# XICIE_AFE_SMD_revA.net
KiCad netlist of a schematic drawn in EAGLE
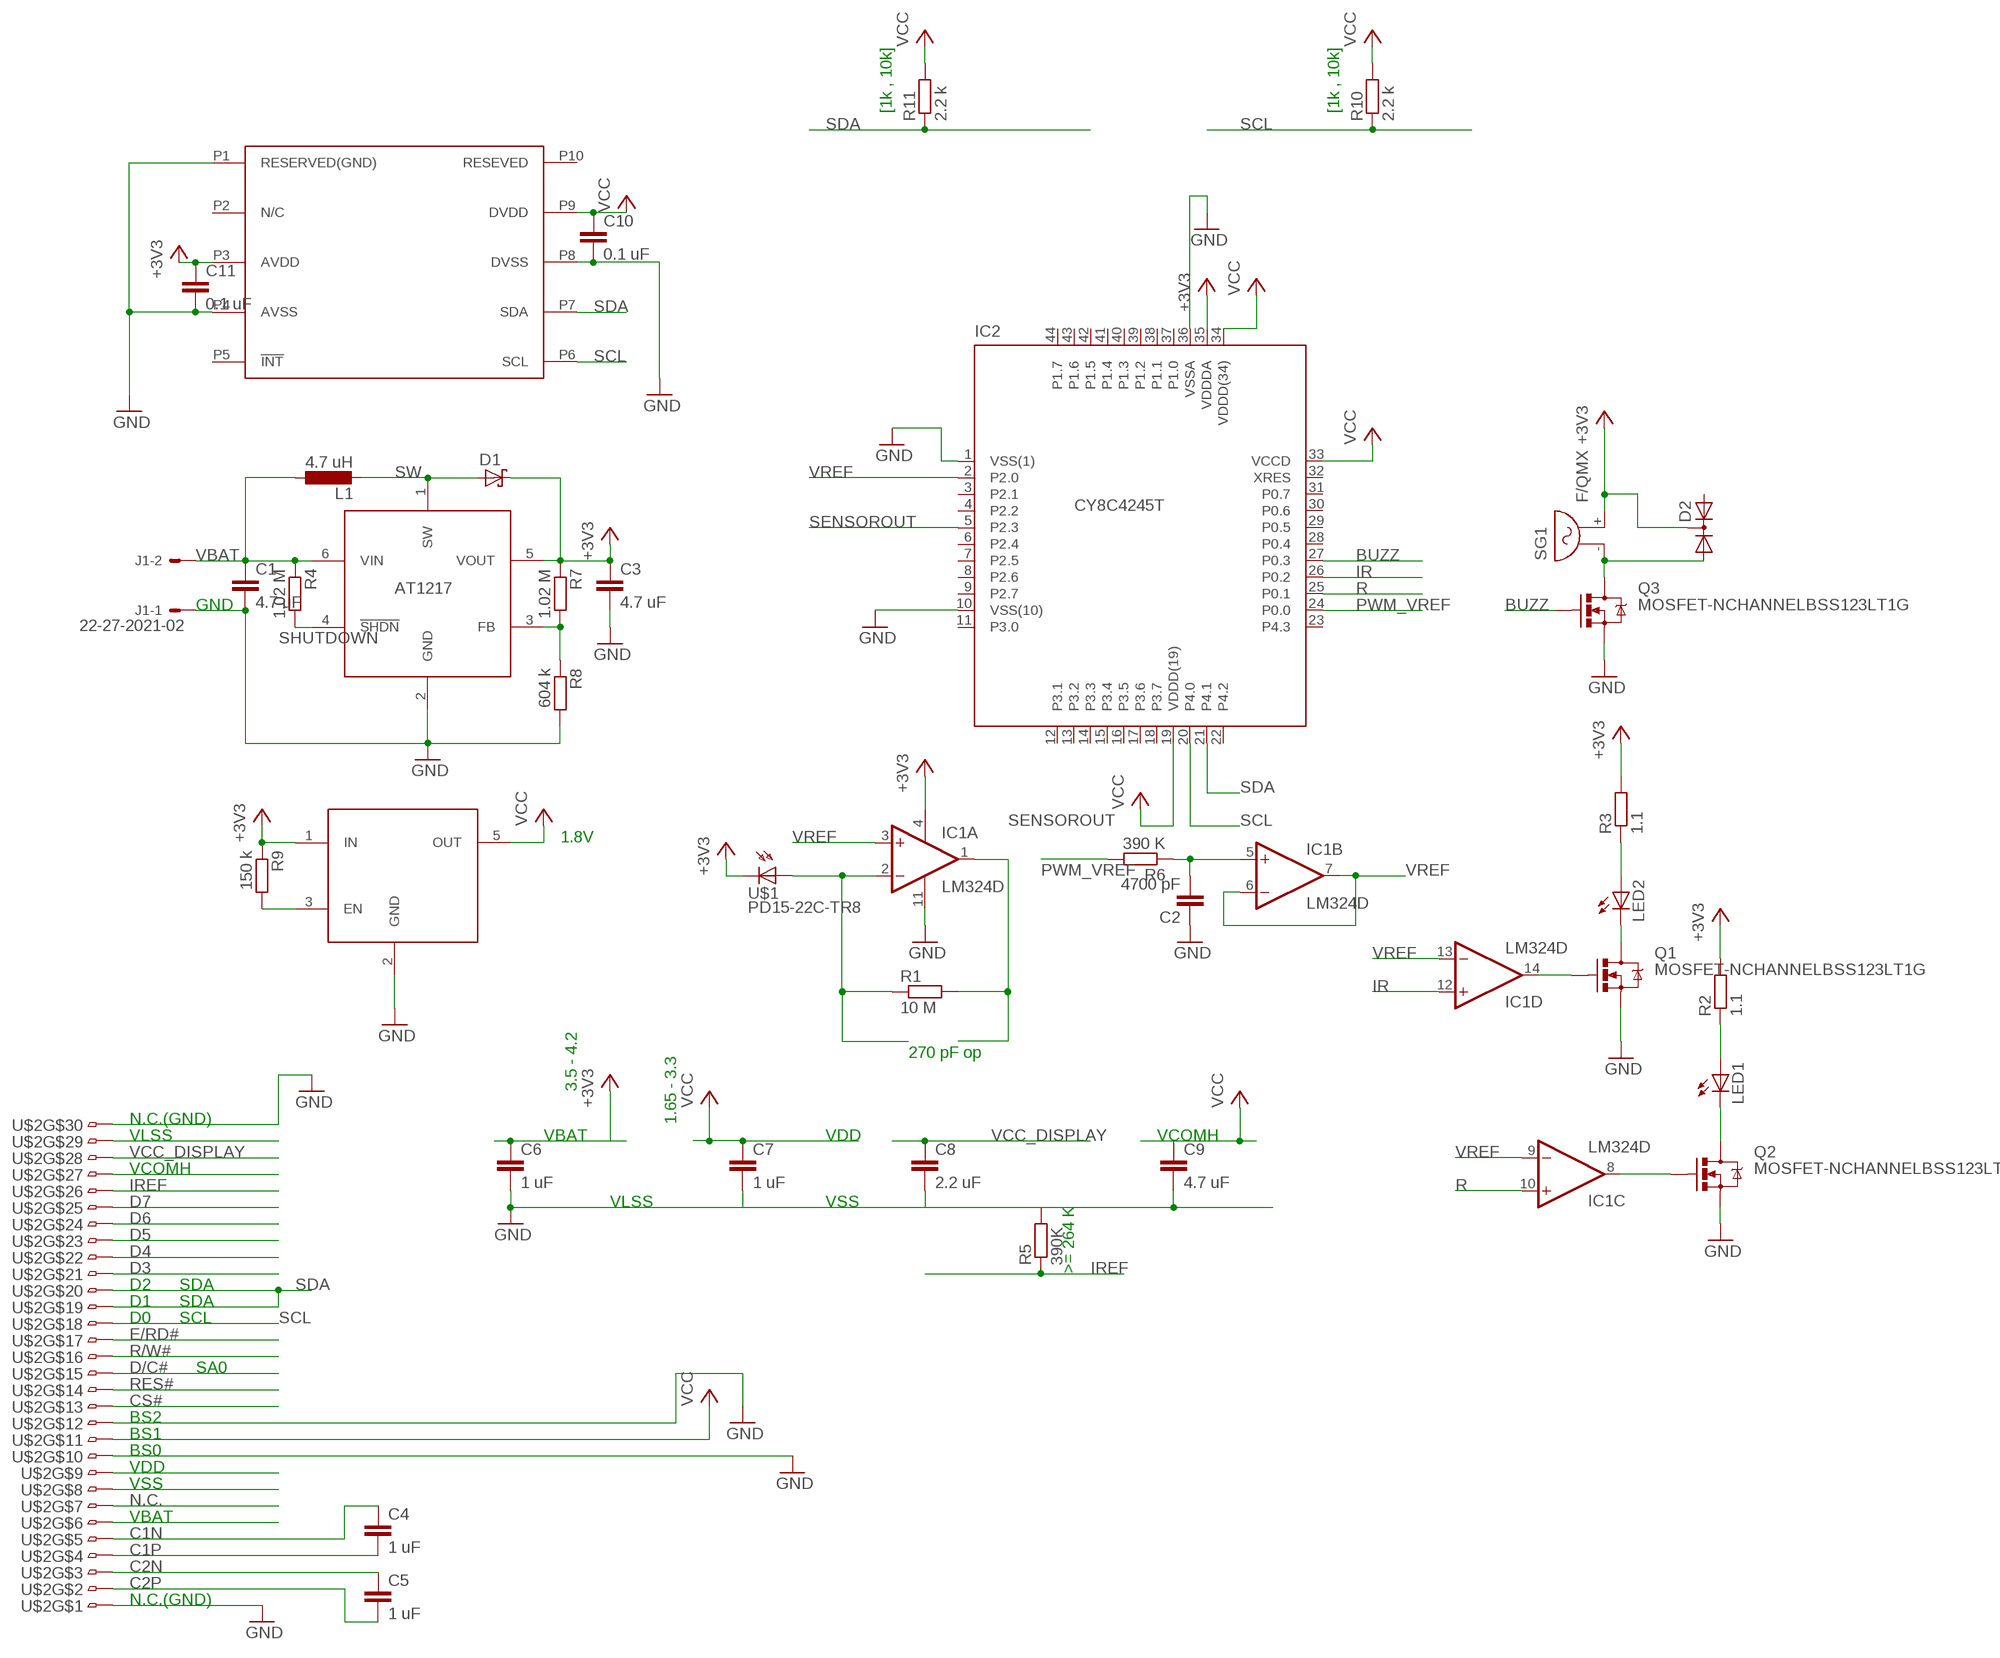
[diagram p0: schematic, sheet 1]

(export (version "E")
  (design (tool "Eeschema 10.0.6"))
  (components
    (comp (ref "C1")
      (value "4.7 uF")
      (footprint "eagle-import:C0603")
      (libsource (lib "eagle-import") (part "C-EUC0603"))
    )
    (comp (ref "C2")
      (value "4700 pF")
      (footprint "eagle-import:C0402")
      (libsource (lib "eagle-import") (part "C-EUC0402"))
    )
    (comp (ref "C3")
      (value "4.7 uF")
      (footprint "eagle-import:C0603")
      (libsource (lib "eagle-import") (part "C-EUC0603"))
    )
    (comp (ref "C4")
      (value "1 uF")
      (footprint "eagle-import:C0402")
      (libsource (lib "eagle-import") (part "C-EUC0402"))
    )
    (comp (ref "C5")
      (value "1 uF")
      (footprint "eagle-import:C0402")
      (libsource (lib "eagle-import") (part "C-EUC0402"))
    )
    (comp (ref "C6")
      (value "1 uF")
      (footprint "eagle-import:C0402")
      (libsource (lib "eagle-import") (part "C-EUC0402"))
    )
    (comp (ref "C7")
      (value "1 uF")
      (footprint "eagle-import:C0402")
      (libsource (lib "eagle-import") (part "C-EUC0402"))
    )
    (comp (ref "C8")
      (value "2.2 uF")
      (footprint "eagle-import:C0603")
      (libsource (lib "eagle-import") (part "C-EUC0603"))
    )
    (comp (ref "C9")
      (value "4.7 uF")
      (footprint "eagle-import:C0603")
      (libsource (lib "eagle-import") (part "C-EUC0603"))
    )
    (comp (ref "C10")
      (value "0.1 uF")
      (footprint "eagle-import:C0402")
      (libsource (lib "eagle-import") (part "C-EUC0402"))
    )
    (comp (ref "C11")
      (value "0.1 uF")
      (footprint "eagle-import:C0402")
      (libsource (lib "eagle-import") (part "C-EUC0402"))
    )
    (comp (ref "D1")
      (value "SCHOTTKY-DIODESMD")
      (footprint "eagle-import:SMINI2-F5-B")
      (libsource (lib "eagle-import") (part "SCHOTTKY-DIODESMD"))
    )
    (comp (ref "D2")
      (value "DIODE-2AC|CASOT23")
      (footprint "eagle-import:SOT23")
      (libsource (lib "eagle-import") (part "DIODE-2AC|CASOT23"))
    )
    (comp (ref "IC1")
      (value "LM324D")
      (footprint "eagle-import:SO14")
      (libsource (lib "eagle-import") (part "LM324D"))
    )
    (comp (ref "IC2")
      (value "CY8C4245T")
      (footprint "eagle-import:TQFP44")
      (libsource (lib "eagle-import") (part "CY8C4245T"))
    )
    (comp (ref "IC3")
      (value "AAT1217")
      (footprint "eagle-import:SOT23-6")
      (libsource (lib "eagle-import") (part "AAT1217"))
    )
    (comp (ref "J1")
      (value "22-27-2021-02")
      (footprint "eagle-import:6410-02")
      (libsource (lib "eagle-import") (part "22-?-0227-2021"))
    )
    (comp (ref "L1")
      (value "4.7 uH")
      (footprint "eagle-import:L2518")
      (libsource (lib "eagle-import") (part "L-EU"))
    )
    (comp (ref "LED1")
      (value "LED5MM")
      (footprint "eagle-import:LED5MM")
      (libsource (lib "eagle-import") (part "LED5MM"))
    )
    (comp (ref "LED2")
      (value "LED5MM")
      (footprint "eagle-import:LED5MM")
      (libsource (lib "eagle-import") (part "LED5MM"))
    )
    (comp (ref "Q1")
      (value "MOSFET-NCHANNELBSS123LT1G")
      (footprint "eagle-import:SOT23")
      (libsource (lib "eagle-import") (part "MOSFET-NCHANNELBSS123LT1G"))
    )
    (comp (ref "Q2")
      (value "MOSFET-NCHANNELBSS123LT1G")
      (footprint "eagle-import:SOT23")
      (libsource (lib "eagle-import") (part "MOSFET-NCHANNELBSS123LT1G"))
    )
    (comp (ref "Q3")
      (value "MOSFET-NCHANNELBSS123LT1G")
      (footprint "eagle-import:SOT23")
      (libsource (lib "eagle-import") (part "MOSFET-NCHANNELBSS123LT1G"))
    )
    (comp (ref "R1")
      (value "10 M")
      (footprint "eagle-import:R0402")
      (libsource (lib "eagle-import") (part "R-EU_R0402"))
    )
    (comp (ref "R2")
      (value "1.1")
      (footprint "eagle-import:R0402")
      (libsource (lib "eagle-import") (part "R-EU_R0402"))
    )
    (comp (ref "R3")
      (value "1.1")
      (footprint "eagle-import:R0402")
      (libsource (lib "eagle-import") (part "R-EU_R0402"))
    )
    (comp (ref "R4")
      (value "1.02 M")
      (footprint "eagle-import:R0805")
      (libsource (lib "eagle-import") (part "R-EU_R0805"))
    )
    (comp (ref "R5")
      (value "390K")
      (footprint "eagle-import:R0603")
      (libsource (lib "eagle-import") (part "resistor_R-EU_R0603"))
    )
    (comp (ref "R6")
      (value "390 K")
      (footprint "eagle-import:R0603")
      (libsource (lib "eagle-import") (part "R-EU_R0603"))
    )
    (comp (ref "R7")
      (value "1.02 M")
      (footprint "eagle-import:R0805")
      (libsource (lib "eagle-import") (part "R-EU_R0805"))
    )
    (comp (ref "R8")
      (value "604 k")
      (footprint "eagle-import:R0603")
      (libsource (lib "eagle-import") (part "R-EU_R0603"))
    )
    (comp (ref "R9")
      (value "150 k")
      (footprint "eagle-import:R0603")
      (libsource (lib "eagle-import") (part "R-EU_R0603"))
    )
    (comp (ref "R10")
      (value "2.2 k")
      (footprint "eagle-import:R0402")
      (libsource (lib "eagle-import") (part "R-EU_R0402"))
    )
    (comp (ref "R11")
      (value "2.2 k")
      (footprint "eagle-import:R0402")
      (libsource (lib "eagle-import") (part "R-EU_R0402"))
    )
    (comp (ref "SG1")
      (value "F/QMX")
      (footprint "eagle-import:F_QMX")
      (libsource (lib "eagle-import") (part "F/QMX"))
    )
    (comp (ref "U$1")
      (value "PD15-22C-TR8")
      (footprint "eagle-import:PHOTO_SMD")
      (libsource (lib "eagle-import") (part "PD15-22C-TR8"))
    )
    (comp (ref "U$2")
      (value "ER-OLED0.96")
      (footprint "eagle-import:FLEX0.7X30")
      (libsource (lib "eagle-import") (part "ER-OLED0.96"))
    )
    (comp (ref "U$3")
      (value "AAT3221")
      (footprint "eagle-import:SOT23-5")
      (libsource (lib "eagle-import") (part "AAT3221"))
    )
    (comp (ref "U$4")
      (value "MMA7660FC")
      (footprint "eagle-import:DFN10")
      (libsource (lib "eagle-import") (part "MMA7660FC"))
    )
  )
  (nets
    (net (code "1") (name "+3V3") (class "Default")
      (node (ref "C11") (pin "1") (pinfunction "1_1") (pintype "passive"))
      (node (ref "C3") (pin "1") (pinfunction "1_1") (pintype "passive"))
      (node (ref "C6") (pin "1") (pinfunction "1_1") (pintype "passive"))
      (node (ref "D1") (pin "C") (pinfunction "C_C") (pintype "passive"))
      (node (ref "D2") (pin "3") (pinfunction "C_3") (pintype "passive"))
      (node (ref "IC1") (pin "4") (pinfunction "V+_4") (pintype "power_in"))
      (node (ref "IC2") (pin "35") (pinfunction "VDDDA_35") (pintype "bidirectional"))
      (node (ref "IC3") (pin "5") (pinfunction "VOUT_5") (pintype "bidirectional"))
      (node (ref "R2") (pin "2") (pinfunction "2_2") (pintype "passive"))
      (node (ref "R3") (pin "2") (pinfunction "2_2") (pintype "passive"))
      (node (ref "R7") (pin "1") (pinfunction "1_1") (pintype "passive"))
      (node (ref "R9") (pin "1") (pinfunction "1_1") (pintype "passive"))
      (node (ref "SG1") (pin "+") (pinfunction "2_+") (pintype "passive"))
      (node (ref "U$1") (pin "CATHODE1") (pinfunction "C_CATHODE1") (pintype "passive"))
      (node (ref "U$1") (pin "CATHODE2") (pinfunction "C_CATHODE2") (pintype "passive"))
      (node (ref "U$2") (pin "P6") (pinfunction "1_P6") (pintype "passive"))
      (node (ref "U$3") (pin "1") (pinfunction "IN_1") (pintype "bidirectional"))
      (node (ref "U$4") (pin "P3") (pinfunction "AVDD_P3") (pintype "bidirectional"))
    )
    (net (code "2") (name "/BUZZ") (class "Default")
      (node (ref "IC2") (pin "27") (pinfunction "P0.3_27") (pintype "bidirectional"))
      (node (ref "Q3") (pin "1") (pinfunction "G_1") (pintype "passive"))
    )
    (net (code "3") (name "/C1N") (class "Default")
      (node (ref "C4") (pin "1") (pinfunction "1_1") (pintype "passive"))
      (node (ref "U$2") (pin "P5") (pinfunction "1_P5") (pintype "passive"))
    )
    (net (code "4") (name "/C1P") (class "Default")
      (node (ref "C4") (pin "2") (pinfunction "2_2") (pintype "passive"))
      (node (ref "U$2") (pin "P4") (pinfunction "1_P4") (pintype "passive"))
    )
    (net (code "5") (name "/C2N") (class "Default")
      (node (ref "C5") (pin "1") (pinfunction "1_1") (pintype "passive"))
      (node (ref "U$2") (pin "P3") (pinfunction "1_P3") (pintype "passive"))
    )
    (net (code "6") (name "/C2P") (class "Default")
      (node (ref "C5") (pin "2") (pinfunction "2_2") (pintype "passive"))
      (node (ref "U$2") (pin "P2") (pinfunction "1_P2") (pintype "passive"))
    )
    (net (code "7") (name "/CS#") (class "Default")
      (node (ref "U$2") (pin "P13") (pinfunction "1_P13") (pintype "passive"))
    )
    (net (code "8") (name "/D3") (class "Default")
      (node (ref "U$2") (pin "P21") (pinfunction "1_P21") (pintype "passive"))
    )
    (net (code "9") (name "/D4") (class "Default")
      (node (ref "U$2") (pin "P22") (pinfunction "1_P22") (pintype "passive"))
    )
    (net (code "10") (name "/D5") (class "Default")
      (node (ref "U$2") (pin "P23") (pinfunction "1_P23") (pintype "passive"))
    )
    (net (code "11") (name "/D6") (class "Default")
      (node (ref "U$2") (pin "P24") (pinfunction "1_P24") (pintype "passive"))
    )
    (net (code "12") (name "/D7") (class "Default")
      (node (ref "U$2") (pin "P25") (pinfunction "1_P25") (pintype "passive"))
    )
    (net (code "13") (name "/D{slash}C#") (class "Default")
      (node (ref "U$2") (pin "P15") (pinfunction "1_P15") (pintype "passive"))
    )
    (net (code "14") (name "/E{slash}RD#") (class "Default")
      (node (ref "U$2") (pin "P17") (pinfunction "1_P17") (pintype "passive"))
    )
    (net (code "15") (name "/IR") (class "Default")
      (node (ref "IC1") (pin "12") (pinfunction "+IN_12") (pintype "input"))
      (node (ref "IC2") (pin "26") (pinfunction "P0.2_26") (pintype "input"))
    )
    (net (code "16") (name "/IREF") (class "Default")
      (node (ref "R5") (pin "1") (pinfunction "1_1") (pintype "passive"))
      (node (ref "U$2") (pin "P26") (pinfunction "1_P26") (pintype "passive"))
    )
    (net (code "17") (name "/N.C.") (class "Default")
      (node (ref "U$2") (pin "P7") (pinfunction "1_P7") (pintype "passive"))
    )
    (net (code "18") (name "/P0.6") (class "Default")
      (node (ref "IC2") (pin "30") (pinfunction "P0.6_30") (pintype "power_in"))
    )
    (net (code "19") (name "/P1.2") (class "Default")
      (node (ref "IC2") (pin "39") (pinfunction "P1.2_39") (pintype "power_in"))
    )
    (net (code "20") (name "/P2.2") (class "Default")
      (node (ref "IC2") (pin "4") (pinfunction "P2.2_4") (pintype "power_in"))
    )
    (net (code "21") (name "/P2.6") (class "Default")
      (node (ref "IC2") (pin "8") (pinfunction "P2.6_8") (pintype "power_in"))
    )
    (net (code "22") (name "/P3.6") (class "Default")
      (node (ref "IC2") (pin "17") (pinfunction "P3.6_17") (pintype "power_in"))
    )
    (net (code "23") (name "/PWM_VREF") (class "Default")
      (node (ref "IC2") (pin "24") (pinfunction "P0.0_24") (pintype "bidirectional"))
      (node (ref "R6") (pin "2") (pinfunction "2_2") (pintype "passive"))
    )
    (net (code "24") (name "/R") (class "Default")
      (node (ref "IC1") (pin "10") (pinfunction "+IN_10") (pintype "input"))
      (node (ref "IC2") (pin "25") (pinfunction "P0.1_25") (pintype "bidirectional"))
    )
    (net (code "25") (name "/RES#") (class "Default")
      (node (ref "U$2") (pin "P14") (pinfunction "1_P14") (pintype "passive"))
    )
    (net (code "26") (name "/R{slash}W#") (class "Default")
      (node (ref "U$2") (pin "P16") (pinfunction "1_P16") (pintype "passive"))
    )
    (net (code "27") (name "/SCL") (class "Default")
      (node (ref "IC2") (pin "20") (pinfunction "P4.0_20") (pintype "bidirectional"))
      (node (ref "R10") (pin "1") (pinfunction "1_1") (pintype "passive"))
      (node (ref "U$2") (pin "P18") (pinfunction "1_P18") (pintype "passive"))
      (node (ref "U$4") (pin "P6") (pinfunction "SCL_P6") (pintype "bidirectional"))
    )
    (net (code "28") (name "/SDA") (class "Default")
      (node (ref "IC2") (pin "21") (pinfunction "P4.1_21") (pintype "bidirectional"))
      (node (ref "R11") (pin "1") (pinfunction "1_1") (pintype "passive"))
      (node (ref "U$2") (pin "P19") (pinfunction "1_P19") (pintype "passive"))
      (node (ref "U$2") (pin "P20") (pinfunction "1_P20") (pintype "passive"))
      (node (ref "U$4") (pin "P7") (pinfunction "SDA_P7") (pintype "bidirectional"))
    )
    (net (code "29") (name "/SENSOROUT") (class "Default")
      (node (ref "IC1") (pin "1") (pinfunction "OUT_1") (pintype "output"))
      (node (ref "IC2") (pin "5") (pinfunction "P2.3_5") (pintype "bidirectional"))
      (node (ref "R1") (pin "2") (pinfunction "2_2") (pintype "passive"))
    )
    (net (code "30") (name "/SHUTDOWN") (class "Default")
      (node (ref "IC3") (pin "4") (pinfunction "~{SHDN}_4") (pintype "bidirectional"))
      (node (ref "R4") (pin "2") (pinfunction "2_2") (pintype "passive"))
    )
    (net (code "31") (name "/SW") (class "Default")
      (node (ref "D1") (pin "A") (pinfunction "A_A") (pintype "passive"))
      (node (ref "IC3") (pin "1") (pinfunction "SW_1") (pintype "bidirectional"))
      (node (ref "L1") (pin "2") (pinfunction "2_2") (pintype "passive"))
    )
    (net (code "32") (name "/VBAT") (class "Default")
      (node (ref "C1") (pin "1") (pinfunction "1_1") (pintype "passive"))
      (node (ref "IC3") (pin "6") (pinfunction "VIN_6") (pintype "bidirectional"))
      (node (ref "J1") (pin "2") (pinfunction "S_2") (pintype "passive"))
      (node (ref "L1") (pin "1") (pinfunction "1_1") (pintype "passive"))
      (node (ref "R4") (pin "1") (pinfunction "1_1") (pintype "passive"))
    )
    (net (code "33") (name "/VCC_DISPLAY") (class "Default")
      (node (ref "C8") (pin "1") (pinfunction "1_1") (pintype "passive"))
      (node (ref "U$2") (pin "P28") (pinfunction "1_P28") (pintype "passive"))
    )
    (net (code "34") (name "/VREF") (class "Default")
      (node (ref "IC1") (pin "13") (pinfunction "-IN_13") (pintype "input"))
      (node (ref "IC1") (pin "3") (pinfunction "+IN_3") (pintype "input"))
      (node (ref "IC1") (pin "6") (pinfunction "-IN_6") (pintype "input"))
      (node (ref "IC1") (pin "7") (pinfunction "OUT_7") (pintype "output"))
      (node (ref "IC1") (pin "9") (pinfunction "-IN_9") (pintype "input"))
      (node (ref "IC2") (pin "2") (pinfunction "P2.0_2") (pintype "bidirectional"))
    )
    (net (code "35") (name "GND") (class "Default")
      (node (ref "C1") (pin "2") (pinfunction "2_2") (pintype "passive"))
      (node (ref "C10") (pin "2") (pinfunction "2_2") (pintype "passive"))
      (node (ref "C11") (pin "2") (pinfunction "2_2") (pintype "passive"))
      (node (ref "C2") (pin "1") (pinfunction "1_1") (pintype "passive"))
      (node (ref "C3") (pin "2") (pinfunction "2_2") (pintype "passive"))
      (node (ref "C6") (pin "2") (pinfunction "2_2") (pintype "passive"))
      (node (ref "C7") (pin "2") (pinfunction "2_2") (pintype "passive"))
      (node (ref "C8") (pin "2") (pinfunction "2_2") (pintype "passive"))
      (node (ref "C9") (pin "2") (pinfunction "2_2") (pintype "passive"))
      (node (ref "IC1") (pin "11") (pinfunction "V-_11") (pintype "power_in"))
      (node (ref "IC2") (pin "1") (pinfunction "VSS(1)_1") (pintype "bidirectional"))
      (node (ref "IC2") (pin "10") (pinfunction "VSS(10)_10") (pintype "bidirectional"))
      (node (ref "IC2") (pin "36") (pinfunction "VSSA_36") (pintype "bidirectional"))
      (node (ref "IC3") (pin "2") (pinfunction "GND_2") (pintype "bidirectional"))
      (node (ref "J1") (pin "1") (pinfunction "S_1") (pintype "passive"))
      (node (ref "Q1") (pin "2") (pinfunction "S_2") (pintype "passive"))
      (node (ref "Q2") (pin "2") (pinfunction "S_2") (pintype "passive"))
      (node (ref "Q3") (pin "2") (pinfunction "S_2") (pintype "passive"))
      (node (ref "R5") (pin "2") (pinfunction "2_2") (pintype "passive"))
      (node (ref "R8") (pin "2") (pinfunction "2_2") (pintype "passive"))
      (node (ref "U$2") (pin "P1") (pinfunction "1_P1") (pintype "passive"))
      (node (ref "U$2") (pin "P10") (pinfunction "1_P10") (pintype "passive"))
      (node (ref "U$2") (pin "P12") (pinfunction "1_P12") (pintype "passive"))
      (node (ref "U$2") (pin "P29") (pinfunction "1_P29") (pintype "passive"))
      (node (ref "U$2") (pin "P30") (pinfunction "1_P30") (pintype "passive"))
      (node (ref "U$2") (pin "P8") (pinfunction "1_P8") (pintype "passive"))
      (node (ref "U$3") (pin "2") (pinfunction "GND_2") (pintype "bidirectional"))
      (node (ref "U$4") (pin "P1") (pinfunction "RESERVED(GND)_P1") (pintype "bidirectional"))
      (node (ref "U$4") (pin "P4") (pinfunction "AVSS_P4") (pintype "bidirectional"))
      (node (ref "U$4") (pin "P8") (pinfunction "DVSS_P8") (pintype "bidirectional"))
    )
    (net (code "36") (name "Net-(D2-A1)") (class "Default")
      (node (ref "D2") (pin "1") (pinfunction "A1_1") (pintype "passive"))
      (node (ref "Q3") (pin "3") (pinfunction "D_3") (pintype "passive"))
      (node (ref "SG1") (pin "-") (pinfunction "1_-") (pintype "passive"))
    )
    (net (code "37") (name "Net-(IC1A--IN)") (class "Default")
      (node (ref "IC1") (pin "2") (pinfunction "-IN_2") (pintype "input"))
      (node (ref "R1") (pin "1") (pinfunction "1_1") (pintype "passive"))
      (node (ref "U$1") (pin "ANODE1") (pinfunction "A_ANODE1") (pintype "passive"))
      (node (ref "U$1") (pin "ANODE2") (pinfunction "A_ANODE2") (pintype "passive"))
    )
    (net (code "38") (name "Net-(IC1B-+IN)") (class "Default")
      (node (ref "C2") (pin "2") (pinfunction "2_2") (pintype "passive"))
      (node (ref "IC1") (pin "5") (pinfunction "+IN_5") (pintype "input"))
      (node (ref "R6") (pin "1") (pinfunction "1_1") (pintype "passive"))
    )
    (net (code "39") (name "Net-(IC1C-OUT)") (class "Default")
      (node (ref "IC1") (pin "8") (pinfunction "OUT_8") (pintype "output"))
      (node (ref "Q2") (pin "1") (pinfunction "G_1") (pintype "passive"))
    )
    (net (code "40") (name "Net-(IC1D-OUT)") (class "Default")
      (node (ref "IC1") (pin "14") (pinfunction "OUT_14") (pintype "output"))
      (node (ref "Q1") (pin "1") (pinfunction "G_1") (pintype "passive"))
    )
    (net (code "41") (name "Net-(IC3-FB)") (class "Default")
      (node (ref "IC3") (pin "3") (pinfunction "FB_3") (pintype "bidirectional"))
      (node (ref "R7") (pin "2") (pinfunction "2_2") (pintype "passive"))
      (node (ref "R8") (pin "1") (pinfunction "1_1") (pintype "passive"))
    )
    (net (code "42") (name "Net-(LED1-C)") (class "Default")
      (node (ref "LED1") (pin "K") (pinfunction "C_K") (pintype "passive"))
      (node (ref "Q2") (pin "3") (pinfunction "D_3") (pintype "passive"))
    )
    (net (code "43") (name "Net-(LED1-PadA)") (class "Default")
      (node (ref "LED1") (pin "A") (pinfunction "A_A") (pintype "passive"))
      (node (ref "R2") (pin "1") (pinfunction "1_1") (pintype "passive"))
    )
    (net (code "44") (name "Net-(LED2-C)") (class "Default")
      (node (ref "LED2") (pin "K") (pinfunction "C_K") (pintype "passive"))
      (node (ref "Q1") (pin "3") (pinfunction "D_3") (pintype "passive"))
    )
    (net (code "45") (name "Net-(LED2-PadA)") (class "Default")
      (node (ref "LED2") (pin "A") (pinfunction "A_A") (pintype "passive"))
      (node (ref "R3") (pin "1") (pinfunction "1_1") (pintype "passive"))
    )
    (net (code "46") (name "Net-(U$3-EN)") (class "Default")
      (node (ref "R9") (pin "2") (pinfunction "2_2") (pintype "passive"))
      (node (ref "U$3") (pin "3") (pinfunction "EN_3") (pintype "bidirectional"))
    )
    (net (code "47") (name "VCC") (class "Default")
      (node (ref "C10") (pin "1") (pinfunction "1_1") (pintype "passive"))
      (node (ref "C7") (pin "1") (pinfunction "1_1") (pintype "passive"))
      (node (ref "C9") (pin "1") (pinfunction "1_1") (pintype "passive"))
      (node (ref "IC2") (pin "19") (pinfunction "VDDD(19)_19") (pintype "bidirectional"))
      (node (ref "IC2") (pin "33") (pinfunction "VCCD_33") (pintype "bidirectional"))
      (node (ref "IC2") (pin "34") (pinfunction "VDDD(34)_34") (pintype "bidirectional"))
      (node (ref "R10") (pin "2") (pinfunction "2_2") (pintype "passive"))
      (node (ref "R11") (pin "2") (pinfunction "2_2") (pintype "passive"))
      (node (ref "U$2") (pin "P11") (pinfunction "1_P11") (pintype "passive"))
      (node (ref "U$2") (pin "P27") (pinfunction "1_P27") (pintype "passive"))
      (node (ref "U$2") (pin "P9") (pinfunction "1_P9") (pintype "passive"))
      (node (ref "U$3") (pin "5") (pinfunction "OUT_5") (pintype "bidirectional"))
      (node (ref "U$4") (pin "P9") (pinfunction "DVDD_P9") (pintype "bidirectional"))
    )
    (net (code "48") (name "unconnected-(D2-A2-Pad2)") (class "Default")
      (node (ref "D2") (pin "2") (pinfunction "A2_2") (pintype "passive"))
    )
    (net (code "49") (name "unconnected-(IC2-P0.4-Pad28)") (class "Default")
      (node (ref "IC2") (pin "28") (pinfunction "P0.4_28") (pintype "bidirectional"))
    )
    (net (code "50") (name "unconnected-(IC2-P0.5-Pad29)") (class "Default")
      (node (ref "IC2") (pin "29") (pinfunction "P0.5_29") (pintype "bidirectional"))
    )
    (net (code "51") (name "unconnected-(IC2-P0.7-Pad31)") (class "Default")
      (node (ref "IC2") (pin "31") (pinfunction "P0.7_31") (pintype "bidirectional"))
    )
    (net (code "52") (name "unconnected-(IC2-P1.0-Pad37)") (class "Default")
      (node (ref "IC2") (pin "37") (pinfunction "P1.0_37") (pintype "bidirectional"))
    )
    (net (code "53") (name "unconnected-(IC2-P1.1-Pad38)") (class "Default")
      (node (ref "IC2") (pin "38") (pinfunction "P1.1_38") (pintype "bidirectional"))
    )
    (net (code "54") (name "unconnected-(IC2-P1.3-Pad40)") (class "Default")
      (node (ref "IC2") (pin "40") (pinfunction "P1.3_40") (pintype "bidirectional"))
    )
    (net (code "55") (name "unconnected-(IC2-P1.4-Pad41)") (class "Default")
      (node (ref "IC2") (pin "41") (pinfunction "P1.4_41") (pintype "bidirectional"))
    )
    (net (code "56") (name "unconnected-(IC2-P1.5-Pad42)") (class "Default")
      (node (ref "IC2") (pin "42") (pinfunction "P1.5_42") (pintype "bidirectional"))
    )
    (net (code "57") (name "unconnected-(IC2-P1.6-Pad43)") (class "Default")
      (node (ref "IC2") (pin "43") (pinfunction "P1.6_43") (pintype "bidirectional"))
    )
    (net (code "58") (name "unconnected-(IC2-P1.7-Pad44)") (class "Default")
      (node (ref "IC2") (pin "44") (pinfunction "P1.7_44") (pintype "bidirectional"))
    )
    (net (code "59") (name "unconnected-(IC2-P2.1-Pad3)") (class "Default")
      (node (ref "IC2") (pin "3") (pinfunction "P2.1_3") (pintype "bidirectional"))
    )
    (net (code "60") (name "unconnected-(IC2-P2.4-Pad6)") (class "Default")
      (node (ref "IC2") (pin "6") (pinfunction "P2.4_6") (pintype "bidirectional"))
    )
    (net (code "61") (name "unconnected-(IC2-P2.5-Pad7)") (class "Default")
      (node (ref "IC2") (pin "7") (pinfunction "P2.5_7") (pintype "bidirectional"))
    )
    (net (code "62") (name "unconnected-(IC2-P2.7-Pad9)") (class "Default")
      (node (ref "IC2") (pin "9") (pinfunction "P2.7_9") (pintype "bidirectional"))
    )
    (net (code "63") (name "unconnected-(IC2-P3.0-Pad11)") (class "Default")
      (node (ref "IC2") (pin "11") (pinfunction "P3.0_11") (pintype "bidirectional"))
    )
    (net (code "64") (name "unconnected-(IC2-P3.1-Pad12)") (class "Default")
      (node (ref "IC2") (pin "12") (pinfunction "P3.1_12") (pintype "bidirectional"))
    )
    (net (code "65") (name "unconnected-(IC2-P3.2-Pad13)") (class "Default")
      (node (ref "IC2") (pin "13") (pinfunction "P3.2_13") (pintype "bidirectional"))
    )
    (net (code "66") (name "unconnected-(IC2-P3.3-Pad14)") (class "Default")
      (node (ref "IC2") (pin "14") (pinfunction "P3.3_14") (pintype "bidirectional"))
    )
    (net (code "67") (name "unconnected-(IC2-P3.4-Pad15)") (class "Default")
      (node (ref "IC2") (pin "15") (pinfunction "P3.4_15") (pintype "bidirectional"))
    )
    (net (code "68") (name "unconnected-(IC2-P3.5-Pad16)") (class "Default")
      (node (ref "IC2") (pin "16") (pinfunction "P3.5_16") (pintype "bidirectional"))
    )
    (net (code "69") (name "unconnected-(IC2-P3.7-Pad18)") (class "Default")
      (node (ref "IC2") (pin "18") (pinfunction "P3.7_18") (pintype "bidirectional"))
    )
    (net (code "70") (name "unconnected-(IC2-P4.2-Pad22)") (class "Default")
      (node (ref "IC2") (pin "22") (pinfunction "P4.2_22") (pintype "bidirectional"))
    )
    (net (code "71") (name "unconnected-(IC2-P4.3-Pad23)") (class "Default")
      (node (ref "IC2") (pin "23") (pinfunction "P4.3_23") (pintype "bidirectional"))
    )
    (net (code "72") (name "unconnected-(IC2-XRES-Pad32)") (class "Default")
      (node (ref "IC2") (pin "32") (pinfunction "XRES_32") (pintype "bidirectional"))
    )
    (net (code "73") (name "unconnected-(U$4-N{slash}C-PadP2)") (class "Default")
      (node (ref "U$4") (pin "P2") (pinfunction "N/C_P2") (pintype "bidirectional"))
    )
    (net (code "74") (name "unconnected-(U$4-RESEVED-PadP10)") (class "Default")
      (node (ref "U$4") (pin "P10") (pinfunction "RESEVED_P10") (pintype "bidirectional"))
    )
    (net (code "75") (name "unconnected-(U$4-~{INT}-PadP5)") (class "Default")
      (node (ref "U$4") (pin "P5") (pinfunction "~{INT}_P5") (pintype "bidirectional"))
    )
  )
)
